# FPGA_POWER_AND_CONFIGURATION.net
KiCad netlist of a schematic drawn in Altium Designer
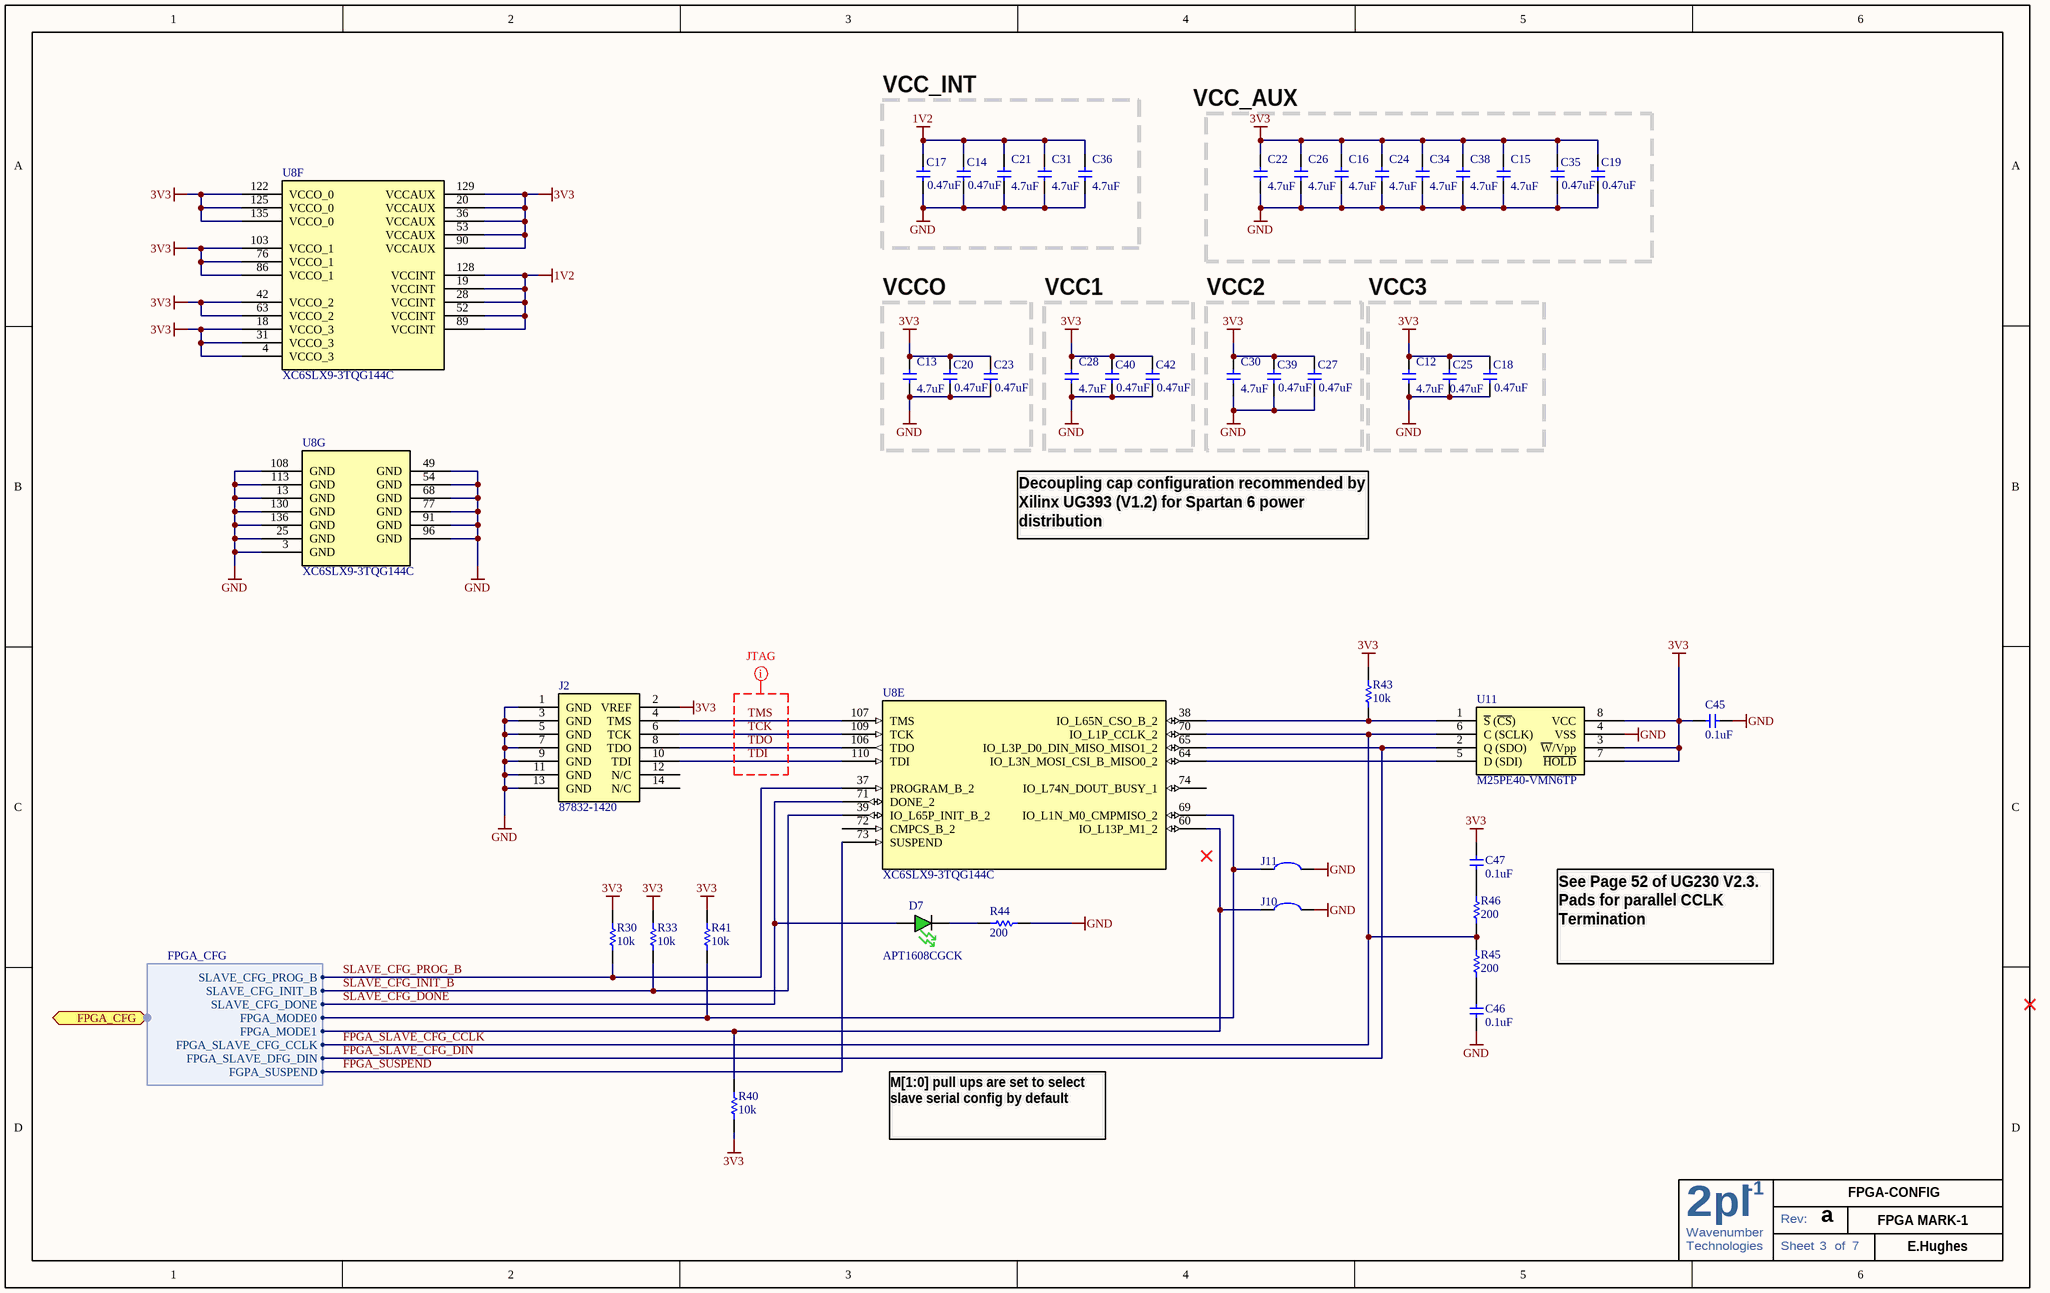
[diagram p0: FPGA_POWER_AND_CONFIGURATION.SchDoc]

(export (version "E")
  (design (tool "Eeschema 10.0.6"))
  (components
    (comp (ref "C12")
      (value "4.7uF")
      (footprint "C0603")
      (description "CAP CER 4.7UF 6.3V X5R 0603")
      (fields
        (field (name "MANUFACTURER") "Murata Electronics North America")
        (field (name "MANUFACTURER PART NUMBER") "GRM188R60J475KE19D")
      )
      (libsource (lib "eCapacitors") (part "GRM188R60J475KE19D"))
    )
    (comp (ref "C13")
      (value "4.7uF")
      (footprint "C0603")
      (description "CAP CER 4.7UF 6.3V X5R 0603")
      (fields
        (field (name "MANUFACTURER") "Murata Electronics North America")
        (field (name "MANUFACTURER PART NUMBER") "GRM188R60J475KE19D")
      )
      (libsource (lib "eCapacitors") (part "GRM188R60J475KE19D"))
    )
    (comp (ref "C14")
      (value "0.47uF")
      (footprint "C0603")
      (description "CAP CER .47UF 25V X7R 0603")
      (fields
        (field (name "MANUFACTURER") "Murata Electronics North America")
        (field (name "MANUFACTURER PART NUMBER") "GCM188R71E474KA64D")
      )
      (libsource (lib "eCapacitors") (part "GCM188R71E474KA64D"))
    )
    (comp (ref "C15")
      (value "4.7uF")
      (footprint "C0603")
      (description "CAP CER 4.7UF 6.3V X5R 0603")
      (fields
        (field (name "MANUFACTURER") "Murata Electronics North America")
        (field (name "MANUFACTURER PART NUMBER") "GRM188R60J475KE19D")
      )
      (libsource (lib "eCapacitors") (part "GRM188R60J475KE19D"))
    )
    (comp (ref "C16")
      (value "4.7uF")
      (footprint "C0603")
      (description "CAP CER 4.7UF 6.3V X5R 0603")
      (fields
        (field (name "MANUFACTURER") "Murata Electronics North America")
        (field (name "MANUFACTURER PART NUMBER") "GRM188R60J475KE19D")
      )
      (libsource (lib "eCapacitors") (part "GRM188R60J475KE19D"))
    )
    (comp (ref "C17")
      (value "0.47uF")
      (footprint "C0603")
      (description "CAP CER .47UF 25V X7R 0603")
      (fields
        (field (name "MANUFACTURER") "Murata Electronics North America")
        (field (name "MANUFACTURER PART NUMBER") "GCM188R71E474KA64D")
      )
      (libsource (lib "eCapacitors") (part "GCM188R71E474KA64D"))
    )
    (comp (ref "C18")
      (value "0.47uF")
      (footprint "C0603")
      (description "CAP CER .47UF 25V X7R 0603")
      (fields
        (field (name "MANUFACTURER") "Murata Electronics North America")
        (field (name "MANUFACTURER PART NUMBER") "GCM188R71E474KA64D")
      )
      (libsource (lib "eCapacitors") (part "GCM188R71E474KA64D"))
    )
    (comp (ref "C19")
      (value "0.47uF")
      (footprint "C0603")
      (description "CAP CER .47UF 25V X7R 0603")
      (fields
        (field (name "MANUFACTURER") "Murata Electronics North America")
        (field (name "MANUFACTURER PART NUMBER") "GCM188R71E474KA64D")
      )
      (libsource (lib "eCapacitors") (part "GCM188R71E474KA64D"))
    )
    (comp (ref "C20")
      (value "0.47uF")
      (footprint "C0603")
      (description "CAP CER .47UF 25V X7R 0603")
      (fields
        (field (name "MANUFACTURER") "Murata Electronics North America")
        (field (name "MANUFACTURER PART NUMBER") "GCM188R71E474KA64D")
      )
      (libsource (lib "eCapacitors") (part "GCM188R71E474KA64D"))
    )
    (comp (ref "C21")
      (value "4.7uF")
      (footprint "C0603")
      (description "CAP CER 4.7UF 6.3V X5R 0603")
      (fields
        (field (name "MANUFACTURER") "Murata Electronics North America")
        (field (name "MANUFACTURER PART NUMBER") "GRM188R60J475KE19D")
      )
      (libsource (lib "eCapacitors") (part "GRM188R60J475KE19D"))
    )
    (comp (ref "C22")
      (value "4.7uF")
      (footprint "C0603")
      (description "CAP CER 4.7UF 6.3V X5R 0603")
      (fields
        (field (name "MANUFACTURER") "Murata Electronics North America")
        (field (name "MANUFACTURER PART NUMBER") "GRM188R60J475KE19D")
      )
      (libsource (lib "eCapacitors") (part "GRM188R60J475KE19D"))
    )
    (comp (ref "C23")
      (value "0.47uF")
      (footprint "C0603")
      (description "CAP CER .47UF 25V X7R 0603")
      (fields
        (field (name "MANUFACTURER") "Murata Electronics North America")
        (field (name "MANUFACTURER PART NUMBER") "GCM188R71E474KA64D")
      )
      (libsource (lib "eCapacitors") (part "GCM188R71E474KA64D"))
    )
    (comp (ref "C24")
      (value "4.7uF")
      (footprint "C0603")
      (description "CAP CER 4.7UF 6.3V X5R 0603")
      (fields
        (field (name "MANUFACTURER") "Murata Electronics North America")
        (field (name "MANUFACTURER PART NUMBER") "GRM188R60J475KE19D")
      )
      (libsource (lib "eCapacitors") (part "GRM188R60J475KE19D"))
    )
    (comp (ref "C25")
      (value "0.47uF")
      (footprint "C0603")
      (description "CAP CER .47UF 25V X7R 0603")
      (fields
        (field (name "MANUFACTURER") "Murata Electronics North America")
        (field (name "MANUFACTURER PART NUMBER") "GCM188R71E474KA64D")
      )
      (libsource (lib "eCapacitors") (part "GCM188R71E474KA64D"))
    )
    (comp (ref "C26")
      (value "4.7uF")
      (footprint "C0603")
      (description "CAP CER 4.7UF 6.3V X5R 0603")
      (fields
        (field (name "MANUFACTURER") "Murata Electronics North America")
        (field (name "MANUFACTURER PART NUMBER") "GRM188R60J475KE19D")
      )
      (libsource (lib "eCapacitors") (part "GRM188R60J475KE19D"))
    )
    (comp (ref "C27")
      (value "0.47uF")
      (footprint "C0603")
      (description "CAP CER .47UF 25V X7R 0603")
      (fields
        (field (name "MANUFACTURER") "Murata Electronics North America")
        (field (name "MANUFACTURER PART NUMBER") "GCM188R71E474KA64D")
      )
      (libsource (lib "eCapacitors") (part "GCM188R71E474KA64D"))
    )
    (comp (ref "C28")
      (value "4.7uF")
      (footprint "C0603")
      (description "CAP CER 4.7UF 6.3V X5R 0603")
      (fields
        (field (name "MANUFACTURER") "Murata Electronics North America")
        (field (name "MANUFACTURER PART NUMBER") "GRM188R60J475KE19D")
      )
      (libsource (lib "eCapacitors") (part "GRM188R60J475KE19D"))
    )
    (comp (ref "C30")
      (value "4.7uF")
      (footprint "C0603")
      (description "CAP CER 4.7UF 6.3V X5R 0603")
      (fields
        (field (name "MANUFACTURER") "Murata Electronics North America")
        (field (name "MANUFACTURER PART NUMBER") "GRM188R60J475KE19D")
      )
      (libsource (lib "eCapacitors") (part "GRM188R60J475KE19D"))
    )
    (comp (ref "C31")
      (value "4.7uF")
      (footprint "C0603")
      (description "CAP CER 4.7UF 6.3V X5R 0603")
      (fields
        (field (name "MANUFACTURER") "Murata Electronics North America")
        (field (name "MANUFACTURER PART NUMBER") "GRM188R60J475KE19D")
      )
      (libsource (lib "eCapacitors") (part "GRM188R60J475KE19D"))
    )
    (comp (ref "C34")
      (value "4.7uF")
      (footprint "C0603")
      (description "CAP CER 4.7UF 6.3V X5R 0603")
      (fields
        (field (name "MANUFACTURER") "Murata Electronics North America")
        (field (name "MANUFACTURER PART NUMBER") "GRM188R60J475KE19D")
      )
      (libsource (lib "eCapacitors") (part "GRM188R60J475KE19D"))
    )
    (comp (ref "C35")
      (value "0.47uF")
      (footprint "C0603")
      (description "CAP CER .47UF 25V X7R 0603")
      (fields
        (field (name "MANUFACTURER") "Murata Electronics North America")
        (field (name "MANUFACTURER PART NUMBER") "GCM188R71E474KA64D")
      )
      (libsource (lib "eCapacitors") (part "GCM188R71E474KA64D"))
    )
    (comp (ref "C36")
      (value "4.7uF")
      (footprint "C0603")
      (description "CAP CER 4.7UF 6.3V X5R 0603")
      (fields
        (field (name "MANUFACTURER") "Murata Electronics North America")
        (field (name "MANUFACTURER PART NUMBER") "GRM188R60J475KE19D")
      )
      (libsource (lib "eCapacitors") (part "GRM188R60J475KE19D"))
    )
    (comp (ref "C38")
      (value "4.7uF")
      (footprint "C0603")
      (description "CAP CER 4.7UF 6.3V X5R 0603")
      (fields
        (field (name "MANUFACTURER") "Murata Electronics North America")
        (field (name "MANUFACTURER PART NUMBER") "GRM188R60J475KE19D")
      )
      (libsource (lib "eCapacitors") (part "GRM188R60J475KE19D"))
    )
    (comp (ref "C39")
      (value "0.47uF")
      (footprint "C0603")
      (description "CAP CER .47UF 25V X7R 0603")
      (fields
        (field (name "MANUFACTURER") "Murata Electronics North America")
        (field (name "MANUFACTURER PART NUMBER") "GCM188R71E474KA64D")
      )
      (libsource (lib "eCapacitors") (part "GCM188R71E474KA64D"))
    )
    (comp (ref "C40")
      (value "0.47uF")
      (footprint "C0603")
      (description "CAP CER .47UF 25V X7R 0603")
      (fields
        (field (name "MANUFACTURER") "Murata Electronics North America")
        (field (name "MANUFACTURER PART NUMBER") "GCM188R71E474KA64D")
      )
      (libsource (lib "eCapacitors") (part "GCM188R71E474KA64D"))
    )
    (comp (ref "C42")
      (value "0.47uF")
      (footprint "C0603")
      (description "CAP CER .47UF 25V X7R 0603")
      (fields
        (field (name "MANUFACTURER") "Murata Electronics North America")
        (field (name "MANUFACTURER PART NUMBER") "GCM188R71E474KA64D")
      )
      (libsource (lib "eCapacitors") (part "GCM188R71E474KA64D"))
    )
    (comp (ref "C45")
      (value "0.1uF")
      (footprint "C0603")
      (description "CAP CER .1UF 50V 10% X7R 0603")
      (fields
        (field (name "MANUFACTURER") "Murata Electronics North America")
        (field (name "MANUFACTURER PART NUMBER") "GRM188R71H104KA93D")
      )
      (libsource (lib "eCapacitors") (part "GRM188R71H104KA93D"))
    )
    (comp (ref "C46")
      (value "0.1uF")
      (footprint "C0603")
      (description "CAP CER .1UF 50V 10% X7R 0603")
      (fields
        (field (name "MANUFACTURER") "Murata Electronics North America")
        (field (name "MANUFACTURER PART NUMBER") "GRM188R71H104KA93D")
      )
      (libsource (lib "eCapacitors") (part "GRM188R71H104KA93D"))
    )
    (comp (ref "C47")
      (value "0.1uF")
      (footprint "C0603")
      (description "CAP CER .1UF 50V 10% X7R 0603")
      (fields
        (field (name "MANUFACTURER") "Murata Electronics North America")
        (field (name "MANUFACTURER PART NUMBER") "GRM188R71H104KA93D")
      )
      (libsource (lib "eCapacitors") (part "GRM188R71H104KA93D"))
    )
    (comp (ref "D7")
      (value "APT1608CGCK")
      (footprint "LED_0603 - GREEN")
      (description "LED 1.6X0.8MM 570NM GRN CLR SMD")
      (fields (field (name "MANUFACTURER") "Kingbright Corp"))
      (libsource (lib "eDiode") (part "APT1608CGCK"))
    )
    (comp (ref "J2")
      (value "87832-1420")
      (footprint "87832-1420")
      (description "CONN HEADER 14POS 2MM VERT SMD")
      (fields (field (name "MANUFACTURER") "Molex Connector Corporation") (field (name "SOURCE") "Digikey"))
      (libsource (lib "eConnector") (part "XILINX_JTAG"))
    )
    (comp (ref "J10")
      (value "Solder Jumper")
      (footprint "SOLDER_JUMPER")
      (description "Solder/Configuration Jumper")
      (fields (field (name "MANUFACTURER") "n/a"))
      (libsource (lib "eConnector") (part "Solder Jumper"))
    )
    (comp (ref "J11")
      (value "Solder Jumper")
      (footprint "SOLDER_JUMPER")
      (description "Solder/Configuration Jumper")
      (fields (field (name "MANUFACTURER") "n/a"))
      (libsource (lib "eConnector") (part "Solder Jumper"))
    )
    (comp (ref "R30")
      (value "10k")
      (footprint "R0603")
      (description "RES 10.0K OHM 1/10W 1% 0603 SMD")
      (fields
        (field (name "MANUFACTURER") "Panasonic - ECG")
        (field (name "MANUFACTURER PART NUMBER") "ERJ-3EKF1002V")
      )
      (libsource (lib "eResistors") (part "ERJ-3EKF1002V"))
    )
    (comp (ref "R33")
      (value "10k")
      (footprint "R0603")
      (description "RES 10.0K OHM 1/10W 1% 0603 SMD")
      (fields
        (field (name "MANUFACTURER") "Panasonic - ECG")
        (field (name "MANUFACTURER PART NUMBER") "ERJ-3EKF1002V")
      )
      (libsource (lib "eResistors") (part "ERJ-3EKF1002V"))
    )
    (comp (ref "R40")
      (value "10k")
      (footprint "R0603")
      (description "RES 10.0K OHM 1/10W 1% 0603 SMD")
      (fields
        (field (name "MANUFACTURER") "Panasonic - ECG")
        (field (name "MANUFACTURER PART NUMBER") "ERJ-3EKF1002V")
      )
      (libsource (lib "eResistors") (part "ERJ-3EKF1002V"))
    )
    (comp (ref "R41")
      (value "10k")
      (footprint "R0603")
      (description "RES 10.0K OHM 1/10W 1% 0603 SMD")
      (fields
        (field (name "MANUFACTURER") "Panasonic - ECG")
        (field (name "MANUFACTURER PART NUMBER") "ERJ-3EKF1002V")
      )
      (libsource (lib "eResistors") (part "ERJ-3EKF1002V"))
    )
    (comp (ref "R43")
      (value "10k")
      (footprint "R0603")
      (description "RES 10.0K OHM 1/10W 1% 0603 SMD")
      (fields
        (field (name "MANUFACTURER") "Panasonic - ECG")
        (field (name "MANUFACTURER PART NUMBER") "ERJ-3EKF1002V")
      )
      (libsource (lib "eResistors") (part "ERJ-3EKF1002V"))
    )
    (comp (ref "R44")
      (value "200")
      (footprint "R0603")
      (description "RES 200 OHM 1/10W 1% 0603 SMD")
      (fields
        (field (name "MANUFACTURER") "Panasonic - ECG")
        (field (name "MANUFACTURER PART NUMBER") "ERJ-3EKF2000V")
      )
      (libsource (lib "eResistors") (part "ERJ-3EKF2000V"))
    )
    (comp (ref "R45")
      (value "200")
      (footprint "R0603")
      (description "RES 200 OHM 1/10W 1% 0603 SMD")
      (fields
        (field (name "MANUFACTURER") "Panasonic - ECG")
        (field (name "MANUFACTURER PART NUMBER") "ERJ-3EKF2000V")
      )
      (libsource (lib "eResistors") (part "ERJ-3EKF2000V"))
    )
    (comp (ref "R46")
      (value "200")
      (footprint "R0603")
      (description "RES 200 OHM 1/10W 1% 0603 SMD")
      (fields
        (field (name "MANUFACTURER") "Panasonic - ECG")
        (field (name "MANUFACTURER PART NUMBER") "ERJ-3EKF2000V")
      )
      (libsource (lib "eResistors") (part "ERJ-3EKF2000V"))
    )
    (comp (ref "U8")
      (value "XC6SLX9-3TQG144C")
      (footprint "TQ144_L")
      (description "IC FPAG SPARTAN 6 9K 144TQFP")
      (fields (field (name "MANUFACTURER") "Xilinx Inc"))
      (libsource (lib "eIC") (part "XC6SLX9-3TQG144C"))
    )
    (comp (ref "U11")
      (value "M25PE40-VMN6TP")
      (footprint "SOIC 8")
      (description "IC FLASH 4MBIT 75MHZ 8SOIC")
      (fields (field (name "MANUFACTURER") "Numonyx - A DIVISION OF MICRON SEMICONDUCTOR PRODUCTS, INC."))
      (libsource (lib "eIC") (part "M25PE40-VMN6TP"))
    )
  )
  (nets
    (net (code "2") (name "/FPGA_SLAVE_CFG_CCLK") (class "Default")
      (node (ref "R45") (pin "2") (pinfunction "2_2") (pintype "passive"))
      (node (ref "R46") (pin "1") (pinfunction "1_1") (pintype "passive"))
      (node (ref "U11") (pin "6") (pinfunction "C_(SCLK)_6") (pintype "passive"))
      (node (ref "U8") (pin "70") (pinfunction "IO_L1P_CCLK_2_70") (pintype "bidirectional"))
    )
    (net (code "3") (name "/FPGA_SLAVE_CFG_DIN") (class "Default")
      (node (ref "U11") (pin "2") (pinfunction "Q_(SDO)_2") (pintype "passive"))
      (node (ref "U8") (pin "65") (pinfunction "IO_L3P_D0_DIN_MISO_MISO1_2_65") (pintype "bidirectional"))
    )
    (net (code "4") (name "/FPGA_SUSPEND") (class "Default")
      (node (ref "U8") (pin "73") (pinfunction "SUSPEND_73") (pintype "input"))
    )
    (net (code "5") (name "/SLAVE_CFG_DONE") (class "Default")
      (node (ref "D7") (pin "A") (pinfunction "A_A") (pintype "passive"))
      (node (ref "U8") (pin "71") (pinfunction "DONE_2_71") (pintype "bidirectional"))
    )
    (net (code "6") (name "/SLAVE_CFG_INIT_B") (class "Default")
      (node (ref "R33") (pin "1") (pinfunction "1_1") (pintype "passive"))
      (node (ref "U8") (pin "39") (pinfunction "IO_L65P_INIT_B_2_39") (pintype "bidirectional"))
    )
    (net (code "7") (name "/SLAVE_CFG_PROG_B") (class "Default")
      (node (ref "R30") (pin "1") (pinfunction "1_1") (pintype "passive"))
      (node (ref "U8") (pin "37") (pinfunction "PROGRAM_B_2_37") (pintype "input"))
    )
    (net (code "8") (name "/TCK") (class "Default")
      (node (ref "J2") (pin "6") (pinfunction "TCK_6") (pintype "passive"))
      (node (ref "U8") (pin "109") (pinfunction "TCK_109") (pintype "input"))
    )
    (net (code "9") (name "/TDI") (class "Default")
      (node (ref "J2") (pin "10") (pinfunction "TDI_10") (pintype "passive"))
      (node (ref "U8") (pin "110") (pinfunction "TDI_110") (pintype "input"))
    )
    (net (code "10") (name "/TDO") (class "Default")
      (node (ref "J2") (pin "8") (pinfunction "TDO_8") (pintype "passive"))
      (node (ref "U8") (pin "106") (pinfunction "TDO_106") (pintype "output"))
    )
    (net (code "11") (name "/TMS") (class "Default")
      (node (ref "J2") (pin "4") (pinfunction "TMS_4") (pintype "passive"))
      (node (ref "U8") (pin "107") (pinfunction "TMS_107") (pintype "input"))
    )
    (net (code "13") (name "1V2") (class "Default")
      (node (ref "C14") (pin "2") (pinfunction "2_2") (pintype "passive"))
      (node (ref "C17") (pin "2") (pinfunction "2_2") (pintype "passive"))
      (node (ref "C21") (pin "2") (pinfunction "2_2") (pintype "passive"))
      (node (ref "C31") (pin "2") (pinfunction "2_2") (pintype "passive"))
      (node (ref "C36") (pin "2") (pinfunction "2_2") (pintype "passive"))
      (node (ref "U8") (pin "128") (pinfunction "VCCINT_128") (pintype "power_in"))
      (node (ref "U8") (pin "19") (pinfunction "VCCINT_19") (pintype "power_in"))
      (node (ref "U8") (pin "28") (pinfunction "VCCINT_28") (pintype "power_in"))
      (node (ref "U8") (pin "52") (pinfunction "VCCINT_52") (pintype "power_in"))
      (node (ref "U8") (pin "89") (pinfunction "VCCINT_89") (pintype "power_in"))
    )
    (net (code "14") (name "3V3") (class "Default")
      (node (ref "C12") (pin "2") (pinfunction "2_2") (pintype "passive"))
      (node (ref "C13") (pin "2") (pinfunction "2_2") (pintype "passive"))
      (node (ref "C15") (pin "2") (pinfunction "2_2") (pintype "passive"))
      (node (ref "C16") (pin "2") (pinfunction "2_2") (pintype "passive"))
      (node (ref "C18") (pin "2") (pinfunction "2_2") (pintype "passive"))
      (node (ref "C19") (pin "2") (pinfunction "2_2") (pintype "passive"))
      (node (ref "C20") (pin "2") (pinfunction "2_2") (pintype "passive"))
      (node (ref "C22") (pin "2") (pinfunction "2_2") (pintype "passive"))
      (node (ref "C23") (pin "2") (pinfunction "2_2") (pintype "passive"))
      (node (ref "C24") (pin "2") (pinfunction "2_2") (pintype "passive"))
      (node (ref "C25") (pin "2") (pinfunction "2_2") (pintype "passive"))
      (node (ref "C26") (pin "2") (pinfunction "2_2") (pintype "passive"))
      (node (ref "C27") (pin "2") (pinfunction "2_2") (pintype "passive"))
      (node (ref "C28") (pin "2") (pinfunction "2_2") (pintype "passive"))
      (node (ref "C30") (pin "2") (pinfunction "2_2") (pintype "passive"))
      (node (ref "C34") (pin "2") (pinfunction "2_2") (pintype "passive"))
      (node (ref "C35") (pin "2") (pinfunction "2_2") (pintype "passive"))
      (node (ref "C38") (pin "2") (pinfunction "2_2") (pintype "passive"))
      (node (ref "C39") (pin "2") (pinfunction "2_2") (pintype "passive"))
      (node (ref "C40") (pin "2") (pinfunction "2_2") (pintype "passive"))
      (node (ref "C42") (pin "2") (pinfunction "2_2") (pintype "passive"))
      (node (ref "C45") (pin "1") (pinfunction "1_1") (pintype "passive"))
      (node (ref "C47") (pin "2") (pinfunction "2_2") (pintype "passive"))
      (node (ref "J2") (pin "2") (pinfunction "VREF_2") (pintype "passive"))
      (node (ref "R30") (pin "2") (pinfunction "2_2") (pintype "passive"))
      (node (ref "R33") (pin "2") (pinfunction "2_2") (pintype "passive"))
      (node (ref "R40") (pin "1") (pinfunction "1_1") (pintype "passive"))
      (node (ref "R41") (pin "2") (pinfunction "2_2") (pintype "passive"))
      (node (ref "R43") (pin "2") (pinfunction "2_2") (pintype "passive"))
      (node (ref "U11") (pin "3") (pinfunction "~{W}/Vpp_3") (pintype "passive"))
      (node (ref "U11") (pin "7") (pinfunction "~{HOLD}_7") (pintype "passive"))
      (node (ref "U11") (pin "8") (pinfunction "VCC_8") (pintype "passive"))
      (node (ref "U8") (pin "103") (pinfunction "VCCO_1_103") (pintype "power_in"))
      (node (ref "U8") (pin "122") (pinfunction "VCCO_0_122") (pintype "power_in"))
      (node (ref "U8") (pin "125") (pinfunction "VCCO_0_125") (pintype "power_in"))
      (node (ref "U8") (pin "129") (pinfunction "VCCAUX_129") (pintype "power_in"))
      (node (ref "U8") (pin "135") (pinfunction "VCCO_0_135") (pintype "power_in"))
      (node (ref "U8") (pin "18") (pinfunction "VCCO_3_18") (pintype "power_in"))
      (node (ref "U8") (pin "20") (pinfunction "VCCAUX_20") (pintype "power_in"))
      (node (ref "U8") (pin "31") (pinfunction "VCCO_3_31") (pintype "power_in"))
      (node (ref "U8") (pin "36") (pinfunction "VCCAUX_36") (pintype "power_in"))
      (node (ref "U8") (pin "4") (pinfunction "VCCO_3_4") (pintype "power_in"))
      (node (ref "U8") (pin "42") (pinfunction "VCCO_2_42") (pintype "power_in"))
      (node (ref "U8") (pin "53") (pinfunction "VCCAUX_53") (pintype "power_in"))
      (node (ref "U8") (pin "63") (pinfunction "VCCO_2_63") (pintype "power_in"))
      (node (ref "U8") (pin "76") (pinfunction "VCCO_1_76") (pintype "power_in"))
      (node (ref "U8") (pin "86") (pinfunction "VCCO_1_86") (pintype "power_in"))
      (node (ref "U8") (pin "90") (pinfunction "VCCAUX_90") (pintype "power_in"))
    )
    (net (code "15") (name "GND") (class "Default")
      (node (ref "C12") (pin "1") (pinfunction "1_1") (pintype "passive"))
      (node (ref "C13") (pin "1") (pinfunction "1_1") (pintype "passive"))
      (node (ref "C14") (pin "1") (pinfunction "1_1") (pintype "passive"))
      (node (ref "C15") (pin "1") (pinfunction "1_1") (pintype "passive"))
      (node (ref "C16") (pin "1") (pinfunction "1_1") (pintype "passive"))
      (node (ref "C17") (pin "1") (pinfunction "1_1") (pintype "passive"))
      (node (ref "C18") (pin "1") (pinfunction "1_1") (pintype "passive"))
      (node (ref "C19") (pin "1") (pinfunction "1_1") (pintype "passive"))
      (node (ref "C20") (pin "1") (pinfunction "1_1") (pintype "passive"))
      (node (ref "C21") (pin "1") (pinfunction "1_1") (pintype "passive"))
      (node (ref "C22") (pin "1") (pinfunction "1_1") (pintype "passive"))
      (node (ref "C23") (pin "1") (pinfunction "1_1") (pintype "passive"))
      (node (ref "C24") (pin "1") (pinfunction "1_1") (pintype "passive"))
      (node (ref "C25") (pin "1") (pinfunction "1_1") (pintype "passive"))
      (node (ref "C26") (pin "1") (pinfunction "1_1") (pintype "passive"))
      (node (ref "C27") (pin "1") (pinfunction "1_1") (pintype "passive"))
      (node (ref "C28") (pin "1") (pinfunction "1_1") (pintype "passive"))
      (node (ref "C30") (pin "1") (pinfunction "1_1") (pintype "passive"))
      (node (ref "C31") (pin "1") (pinfunction "1_1") (pintype "passive"))
      (node (ref "C34") (pin "1") (pinfunction "1_1") (pintype "passive"))
      (node (ref "C35") (pin "1") (pinfunction "1_1") (pintype "passive"))
      (node (ref "C36") (pin "1") (pinfunction "1_1") (pintype "passive"))
      (node (ref "C38") (pin "1") (pinfunction "1_1") (pintype "passive"))
      (node (ref "C39") (pin "1") (pinfunction "1_1") (pintype "passive"))
      (node (ref "C40") (pin "1") (pinfunction "1_1") (pintype "passive"))
      (node (ref "C42") (pin "1") (pinfunction "1_1") (pintype "passive"))
      (node (ref "C45") (pin "2") (pinfunction "2_2") (pintype "passive"))
      (node (ref "C46") (pin "1") (pinfunction "1_1") (pintype "passive"))
      (node (ref "J10") (pin "2") (pinfunction "2_2") (pintype "passive"))
      (node (ref "J11") (pin "2") (pinfunction "2_2") (pintype "passive"))
      (node (ref "J2") (pin "1") (pinfunction "GND_1") (pintype "passive"))
      (node (ref "J2") (pin "11") (pinfunction "GND_11") (pintype "passive"))
      (node (ref "J2") (pin "13") (pinfunction "GND_13") (pintype "passive"))
      (node (ref "J2") (pin "3") (pinfunction "GND_3") (pintype "passive"))
      (node (ref "J2") (pin "5") (pinfunction "GND_5") (pintype "passive"))
      (node (ref "J2") (pin "7") (pinfunction "GND_7") (pintype "passive"))
      (node (ref "J2") (pin "9") (pinfunction "GND_9") (pintype "passive"))
      (node (ref "R44") (pin "2") (pinfunction "2_2") (pintype "passive"))
      (node (ref "U11") (pin "4") (pinfunction "VSS_4") (pintype "passive"))
      (node (ref "U8") (pin "108") (pinfunction "GND_108") (pintype "power_in"))
      (node (ref "U8") (pin "113") (pinfunction "GND_113") (pintype "power_in"))
      (node (ref "U8") (pin "13") (pinfunction "GND_13") (pintype "power_in"))
      (node (ref "U8") (pin "130") (pinfunction "GND_130") (pintype "power_in"))
      (node (ref "U8") (pin "136") (pinfunction "GND_136") (pintype "power_in"))
      (node (ref "U8") (pin "25") (pinfunction "GND_25") (pintype "power_in"))
      (node (ref "U8") (pin "3") (pinfunction "GND_3") (pintype "power_in"))
      (node (ref "U8") (pin "49") (pinfunction "GND_49") (pintype "power_in"))
      (node (ref "U8") (pin "54") (pinfunction "GND_54") (pintype "power_in"))
      (node (ref "U8") (pin "68") (pinfunction "GND_68") (pintype "power_in"))
      (node (ref "U8") (pin "77") (pinfunction "GND_77") (pintype "power_in"))
      (node (ref "U8") (pin "91") (pinfunction "GND_91") (pintype "power_in"))
      (node (ref "U8") (pin "96") (pinfunction "GND_96") (pintype "power_in"))
    )
    (net (code "16") (name "Net-(C46-Pad2)") (class "Default")
      (node (ref "C46") (pin "2") (pinfunction "2_2") (pintype "passive"))
      (node (ref "R45") (pin "1") (pinfunction "1_1") (pintype "passive"))
    )
    (net (code "17") (name "Net-(C47-Pad1)") (class "Default")
      (node (ref "C47") (pin "1") (pinfunction "1_1") (pintype "passive"))
      (node (ref "R46") (pin "2") (pinfunction "2_2") (pintype "passive"))
    )
    (net (code "18") (name "Net-(D7-PadC)") (class "Default")
      (node (ref "D7") (pin "C") (pinfunction "C_C") (pintype "passive"))
      (node (ref "R44") (pin "1") (pinfunction "1_1") (pintype "passive"))
    )
    (net (code "19") (name "Net-(U8E-IO_L1N_M0_CMPMISO_2)") (class "Default")
      (node (ref "J11") (pin "1") (pinfunction "1_1") (pintype "passive"))
      (node (ref "R41") (pin "1") (pinfunction "1_1") (pintype "passive"))
      (node (ref "U8") (pin "69") (pinfunction "IO_L1N_M0_CMPMISO_2_69") (pintype "bidirectional"))
    )
    (net (code "20") (name "Net-(U8E-IO_L13P_M1_2)") (class "Default")
      (node (ref "J10") (pin "1") (pinfunction "1_1") (pintype "passive"))
      (node (ref "R40") (pin "2") (pinfunction "2_2") (pintype "passive"))
      (node (ref "U8") (pin "60") (pinfunction "IO_L13P_M1_2_60") (pintype "bidirectional"))
    )
    (net (code "21") (name "Net-(U11-D_(SDI))") (class "Default")
      (node (ref "U11") (pin "5") (pinfunction "D_(SDI)_5") (pintype "passive"))
      (node (ref "U8") (pin "64") (pinfunction "IO_L3N_MOSI_CSI_B_MISO0_2_64") (pintype "bidirectional"))
    )
    (net (code "22") (name "Net-(U11-~{S}_(~{CS}))") (class "Default")
      (node (ref "R43") (pin "1") (pinfunction "1_1") (pintype "passive"))
      (node (ref "U11") (pin "1") (pinfunction "~{S}_(~{CS})_1") (pintype "passive"))
      (node (ref "U8") (pin "38") (pinfunction "IO_L65N_CSO_B_2_38") (pintype "bidirectional"))
    )
    (net (code "23") (name "unconnected-(J2-N{slash}C-Pad12)") (class "Default")
      (node (ref "J2") (pin "12") (pinfunction "N/C_12") (pintype "passive"))
    )
    (net (code "24") (name "unconnected-(J2-N{slash}C-Pad14)") (class "Default")
      (node (ref "J2") (pin "14") (pinfunction "N/C_14") (pintype "passive"))
    )
    (net (code "25") (name "unconnected-(U8E-CMPCS_B_2-Pad72)") (class "Default")
      (node (ref "U8") (pin "72") (pinfunction "CMPCS_B_2_72") (pintype "input"))
    )
    (net (code "26") (name "unconnected-(U8E-IO_L74N_DOUT_BUSY_1-Pad74)") (class "Default")
      (node (ref "U8") (pin "74") (pinfunction "IO_L74N_DOUT_BUSY_1_74") (pintype "bidirectional"))
    )
  )
)
